# medusa-ai-power.net
KiCad netlist of a schematic drawn in Altium Designer
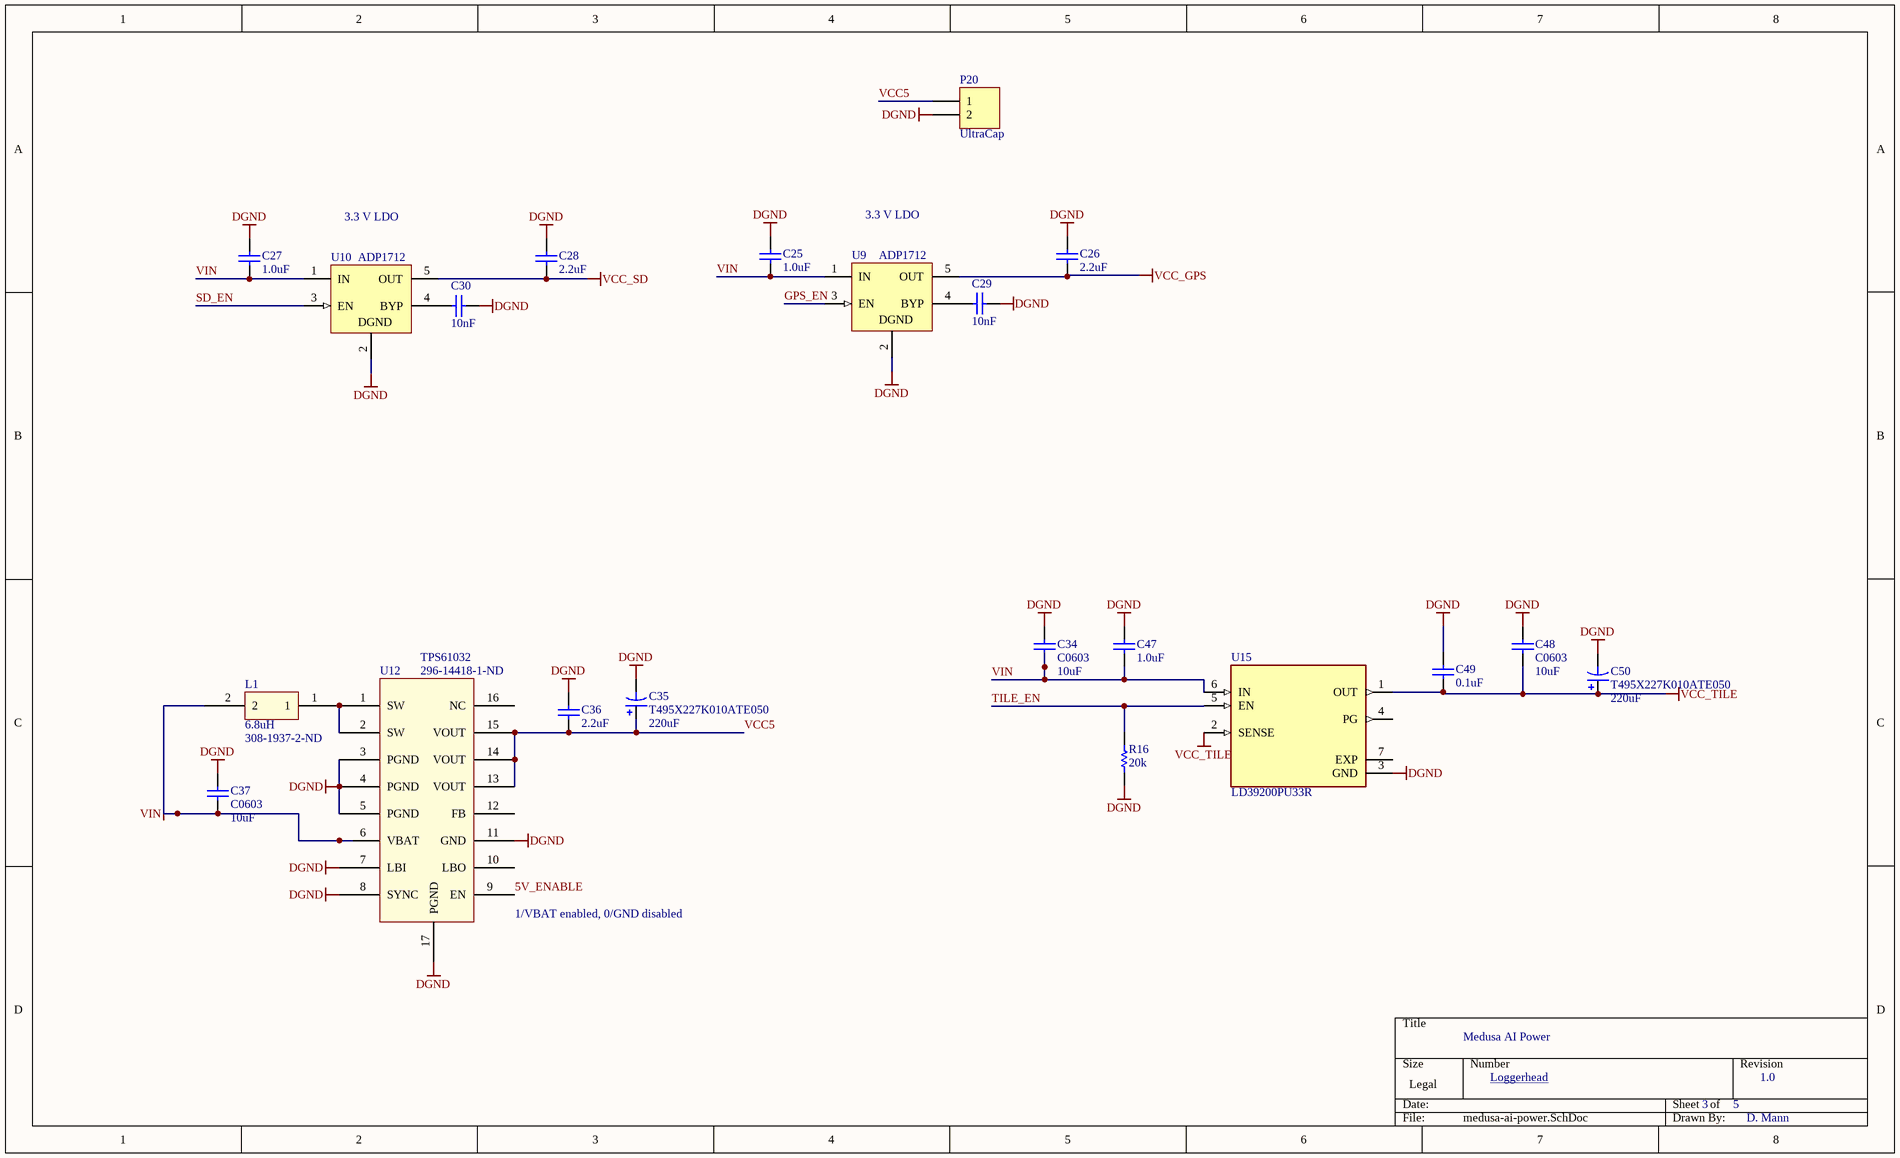
[diagram p0: medusa-ai-power.SchDoc]

(export (version "E")
  (design (tool "Eeschema 10.0.6"))
  (components
    (comp (ref "C25")
      (value "1.0uF")
      (footprint "0402")
      (description "Ceramic Chip Capacitor - Standard")
      (fields (field (name "PUBLISHER") "Altium Limited"))
      (libsource (lib "KEMET Chip Capacitor") (part "C0402"))
    )
    (comp (ref "C26")
      (value "2.2uF")
      (footprint "0402")
      (description "Ceramic Chip Capacitor - Standard")
      (fields (field (name "PUBLISHER") "Altium Limited"))
      (libsource (lib "KEMET Chip Capacitor") (part "C0402"))
    )
    (comp (ref "C27")
      (value "1.0uF")
      (footprint "0402")
      (description "Ceramic Chip Capacitor - Standard")
      (fields (field (name "PUBLISHER") "Altium Limited"))
      (libsource (lib "KEMET Chip Capacitor") (part "C0402"))
    )
    (comp (ref "C28")
      (value "2.2uF")
      (footprint "0402")
      (description "Ceramic Chip Capacitor - Standard")
      (fields (field (name "PUBLISHER") "Altium Limited"))
      (libsource (lib "KEMET Chip Capacitor") (part "C0402"))
    )
    (comp (ref "C29")
      (value "10nF")
      (footprint "0402")
      (description "Ceramic Chip Capacitor - Standard")
      (fields (field (name "PUBLISHER") "Altium Limited"))
      (libsource (lib "KEMET Chip Capacitor") (part "C0402"))
    )
    (comp (ref "C30")
      (value "10nF")
      (footprint "0402")
      (description "Ceramic Chip Capacitor - Standard")
      (fields (field (name "PUBLISHER") "Altium Limited"))
      (libsource (lib "KEMET Chip Capacitor") (part "C0402"))
    )
    (comp (ref "C34")
      (value "C0603")
      (footprint "0603")
      (description "Ceramic Chip Capacitor - Standard")
      (fields (field (name "ALTIUM_VALUE") "10uF") (field (name "PUBLISHER") "Altium Limited"))
      (libsource (lib "KEMET Chip Capacitor") (part "C0603"))
    )
    (comp (ref "C35")
      (value "T495X227K010ATE050")
      (footprint "X")
      (description "Solid Tantalum Chip Capacitor, Standard T495 Series - Low ESR, Surge Robust")
      (fields (field (name "ALTIUM_VALUE") "220uF") (field (name "PUBLISHER") "Altium Limited"))
      (libsource (lib "KEMET Chip Capacitor") (part "T495X"))
    )
    (comp (ref "C36")
      (value "2.2uF")
      (footprint "0402")
      (description "Ceramic Chip Capacitor - Standard")
      (fields (field (name "PUBLISHER") "Altium Limited"))
      (libsource (lib "KEMET Chip Capacitor") (part "C0402"))
    )
    (comp (ref "C37")
      (value "C0603")
      (footprint "0603")
      (description "Ceramic Chip Capacitor - Standard")
      (fields (field (name "ALTIUM_VALUE") "10uF") (field (name "PUBLISHER") "Altium Limited"))
      (libsource (lib "KEMET Chip Capacitor") (part "C0603"))
    )
    (comp (ref "C47")
      (value "1.0uF")
      (footprint "0402")
      (description "Ceramic Chip Capacitor - Standard")
      (fields (field (name "PUBLISHER") "Altium Limited"))
      (libsource (lib "KEMET Chip Capacitor") (part "C0402"))
    )
    (comp (ref "C48")
      (value "C0603")
      (footprint "0603")
      (description "Ceramic Chip Capacitor - Standard")
      (fields (field (name "ALTIUM_VALUE") "10uF") (field (name "PUBLISHER") "Altium Limited"))
      (libsource (lib "KEMET Chip Capacitor") (part "C0603"))
    )
    (comp (ref "C49")
      (value "0.1uF")
      (footprint "0402")
      (description "Ceramic Chip Capacitor - Standard")
      (fields (field (name "PUBLISHER") "Altium Limited"))
      (libsource (lib "KEMET Chip Capacitor") (part "C0402"))
    )
    (comp (ref "C50")
      (value "T495X227K010ATE050")
      (footprint "X")
      (description "Solid Tantalum Chip Capacitor, Standard T495 Series - Low ESR, Surge Robust")
      (fields (field (name "ALTIUM_VALUE") "220uF") (field (name "PUBLISHER") "Altium Limited"))
      (libsource (lib "KEMET Chip Capacitor") (part "T495X"))
    )
    (comp (ref "L1")
      (value "6.8uH")
      (footprint "Inductor - duplicate")
      (description "Sumida Inductor")
      (fields (field (name "SUPPLIER PART NUMBER 1") "308-1937-2-ND"))
      (libsource (lib "Loggerhead") (part "Inductor 6.8uH"))
    )
    (comp (ref "P20")
      (value "UltraCap")
      (footprint "HDR1X2")
      (description "Header, 2-Pin")
      (fields (field (name "PUBLISHER") "Altium Limited"))
      (libsource (lib "Miscellaneous Connectors") (part "Header 2"))
    )
    (comp (ref "R16")
      (value "20k")
      (footprint "3-0603")
      (fields (field (name "PUBLISHER") "Altium Limited"))
      (libsource (lib "Panasonic Resistor") (part "ERJ3RK"))
    )
    (comp (ref "U9")
      (value "ADP1712")
      (footprint "MF05A_N")
      (description "Micropower, 150mA Low-Noise Ultra Low-Dropout CMOS Voltage Regulator")
      (fields
        (field (name "PARTNUMBER") "LP3985IM5-3.3")
        (field (name "MANUFACTURER") "National Semiconductor")
        (field (name "PUBLISHER") "Altium Limited")
      )
      (libsource (lib "NSC LDO") (part "LP3985IM5-3.3"))
    )
    (comp (ref "U10")
      (value "ADP1712")
      (footprint "MF05A_N")
      (description "Micropower, 150mA Low-Noise Ultra Low-Dropout CMOS Voltage Regulator")
      (fields
        (field (name "PARTNUMBER") "LP3985IM5-3.3")
        (field (name "MANUFACTURER") "National Semiconductor")
        (field (name "PUBLISHER") "Altium Limited")
      )
      (libsource (lib "NSC LDO") (part "LP3985IM5-3.3"))
    )
    (comp (ref "U12")
      (value "TPS61032")
      (footprint "TPS6103x")
      (description "Boost converter")
      (fields (field (name "SUPPLIER PART NUMBER 2") "296-14418-1-ND"))
      (libsource (lib "Loggerhead") (part "TPS6103x"))
    )
    (comp (ref "U15")
      (value "LD39200PU33R")
      (footprint "SON95P300X300X100-7N")
      (description "Linear Voltage Regulator IC 1 Output 2A 6-DFN _3x3_")
      (fields (field (name "MF") "STMicroelectronics"))
      (libsource (lib "LD39200PU33R") (part "LD39200PU33R"))
    )
  )
  (nets
    (net (code "1") (name "/5V_ENABLE") (class "Default")
      (node (ref "U12") (pin "9") (pinfunction "EN_9") (pintype "passive"))
    )
    (net (code "2") (name "/GPS_EN") (class "Default")
      (node (ref "U9") (pin "3") (pinfunction "EN_3") (pintype "input"))
    )
    (net (code "3") (name "/SD_EN") (class "Default")
      (node (ref "U10") (pin "3") (pinfunction "EN_3") (pintype "input"))
    )
    (net (code "4") (name "/TILE_EN") (class "Default")
      (node (ref "R16") (pin "1") (pinfunction "1_1") (pintype "passive"))
      (node (ref "U15") (pin "5") (pinfunction "EN_5") (pintype "input"))
    )
    (net (code "5") (name "/VCC5") (class "Default")
      (node (ref "C35") (pin "1") (pinfunction "1_1") (pintype "passive"))
      (node (ref "C36") (pin "1") (pinfunction "1_1") (pintype "passive"))
      (node (ref "P20") (pin "1") (pinfunction "1_1") (pintype "passive"))
      (node (ref "U12") (pin "13") (pinfunction "VOUT_13") (pintype "passive"))
      (node (ref "U12") (pin "14") (pinfunction "VOUT_14") (pintype "passive"))
      (node (ref "U12") (pin "15") (pinfunction "VOUT_15") (pintype "passive"))
    )
    (net (code "6") (name "DGND") (class "Default")
      (node (ref "C25") (pin "2") (pinfunction "2_2") (pintype "passive"))
      (node (ref "C26") (pin "2") (pinfunction "2_2") (pintype "passive"))
      (node (ref "C27") (pin "2") (pinfunction "2_2") (pintype "passive"))
      (node (ref "C28") (pin "2") (pinfunction "2_2") (pintype "passive"))
      (node (ref "C29") (pin "1") (pinfunction "1_1") (pintype "passive"))
      (node (ref "C30") (pin "1") (pinfunction "1_1") (pintype "passive"))
      (node (ref "C34") (pin "1") (pinfunction "1_1") (pintype "passive"))
      (node (ref "C35") (pin "2") (pinfunction "2_2") (pintype "passive"))
      (node (ref "C36") (pin "2") (pinfunction "2_2") (pintype "passive"))
      (node (ref "C37") (pin "1") (pinfunction "1_1") (pintype "passive"))
      (node (ref "C47") (pin "2") (pinfunction "2_2") (pintype "passive"))
      (node (ref "C48") (pin "1") (pinfunction "1_1") (pintype "passive"))
      (node (ref "C49") (pin "2") (pinfunction "2_2") (pintype "passive"))
      (node (ref "C50") (pin "2") (pinfunction "2_2") (pintype "passive"))
      (node (ref "P20") (pin "2") (pinfunction "2_2") (pintype "passive"))
      (node (ref "R16") (pin "2") (pinfunction "2_2") (pintype "passive"))
      (node (ref "U10") (pin "2") (pinfunction "GND_2") (pintype "power_in"))
      (node (ref "U12") (pin "11") (pinfunction "GND_11") (pintype "passive"))
      (node (ref "U12") (pin "17") (pinfunction "PGND_17") (pintype "passive"))
      (node (ref "U12") (pin "3") (pinfunction "PGND_3") (pintype "passive"))
      (node (ref "U12") (pin "4") (pinfunction "PGND_4") (pintype "passive"))
      (node (ref "U12") (pin "5") (pinfunction "PGND_5") (pintype "passive"))
      (node (ref "U12") (pin "7") (pinfunction "LBI_7") (pintype "passive"))
      (node (ref "U12") (pin "8") (pinfunction "SYNC_8") (pintype "passive"))
      (node (ref "U15") (pin "3") (pinfunction "GND_3") (pintype "power_in"))
      (node (ref "U9") (pin "2") (pinfunction "GND_2") (pintype "power_in"))
    )
    (net (code "7") (name "Net-(L1-Pad1)") (class "Default")
      (node (ref "L1") (pin "1") (pinfunction "1_1") (pintype "passive"))
      (node (ref "U12") (pin "1") (pinfunction "SW_1") (pintype "passive"))
      (node (ref "U12") (pin "2") (pinfunction "SW_2") (pintype "passive"))
    )
    (net (code "8") (name "Net-(U9-BYP)") (class "Default")
      (node (ref "C29") (pin "2") (pinfunction "2_2") (pintype "passive"))
      (node (ref "U9") (pin "4") (pinfunction "BYP_4") (pintype "passive"))
    )
    (net (code "9") (name "Net-(U10-BYP)") (class "Default")
      (node (ref "C30") (pin "2") (pinfunction "2_2") (pintype "passive"))
      (node (ref "U10") (pin "4") (pinfunction "BYP_4") (pintype "passive"))
    )
    (net (code "10") (name "VCC_GPS") (class "Default")
      (node (ref "C26") (pin "1") (pinfunction "1_1") (pintype "passive"))
      (node (ref "U9") (pin "5") (pinfunction "OUT_5") (pintype "power_in"))
    )
    (net (code "11") (name "VCC_SD") (class "Default")
      (node (ref "C28") (pin "1") (pinfunction "1_1") (pintype "passive"))
      (node (ref "U10") (pin "5") (pinfunction "OUT_5") (pintype "power_in"))
    )
    (net (code "12") (name "VCC_TILE") (class "Default")
      (node (ref "C48") (pin "2") (pinfunction "2_2") (pintype "passive"))
      (node (ref "C49") (pin "1") (pinfunction "1_1") (pintype "passive"))
      (node (ref "C50") (pin "1") (pinfunction "1_1") (pintype "passive"))
      (node (ref "U15") (pin "1") (pinfunction "OUT_1") (pintype "output"))
      (node (ref "U15") (pin "2") (pinfunction "SENSE_2") (pintype "input"))
    )
    (net (code "13") (name "VIN") (class "Default")
      (node (ref "C25") (pin "1") (pinfunction "1_1") (pintype "passive"))
      (node (ref "C27") (pin "1") (pinfunction "1_1") (pintype "passive"))
      (node (ref "C34") (pin "2") (pinfunction "2_2") (pintype "passive"))
      (node (ref "C37") (pin "2") (pinfunction "2_2") (pintype "passive"))
      (node (ref "C47") (pin "1") (pinfunction "1_1") (pintype "passive"))
      (node (ref "L1") (pin "2") (pinfunction "2_2") (pintype "passive"))
      (node (ref "U10") (pin "1") (pinfunction "IN_1") (pintype "power_in"))
      (node (ref "U12") (pin "6") (pinfunction "VBAT_6") (pintype "passive"))
      (node (ref "U15") (pin "6") (pinfunction "IN_6") (pintype "input"))
      (node (ref "U9") (pin "1") (pinfunction "IN_1") (pintype "power_in"))
    )
    (net (code "14") (name "unconnected-(U12-FB-Pad12)") (class "Default")
      (node (ref "U12") (pin "12") (pinfunction "FB_12") (pintype "passive"))
    )
    (net (code "15") (name "unconnected-(U12-LBO-Pad10)") (class "Default")
      (node (ref "U12") (pin "10") (pinfunction "LBO_10") (pintype "passive"))
    )
    (net (code "16") (name "unconnected-(U12-NC-Pad16)") (class "Default")
      (node (ref "U12") (pin "16") (pinfunction "NC_16") (pintype "passive"))
    )
    (net (code "17") (name "unconnected-(U15-EXP-Pad7)") (class "Default")
      (node (ref "U15") (pin "7") (pinfunction "EXP_7") (pintype "power_in"))
    )
    (net (code "18") (name "unconnected-(U15-PG-Pad4)") (class "Default")
      (node (ref "U15") (pin "4") (pinfunction "PG_4") (pintype "output"))
    )
  )
)
